# PickPlaceFeederSCH.net
KiCad netlist of a schematic drawn in Altium Designer
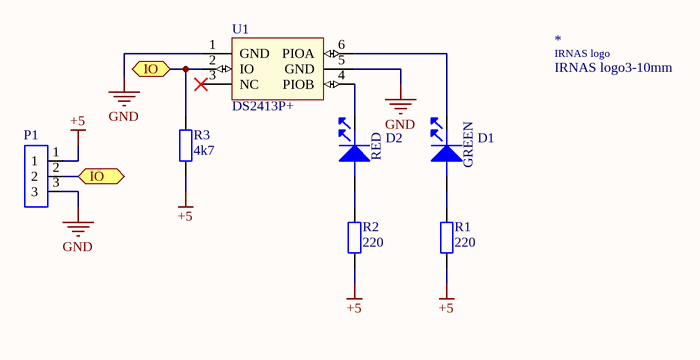
[diagram p0: PickPlaceFeederSCH.SchDoc]

(export (version "E")
  (design (tool "Eeschema 10.0.6"))
  (components
    (comp (ref "*")
      (value "IRNAS logo3-10mm")
      (footprint "LOGO_3-10mm")
      (libsource (lib "Graphical") (part "IRNAS logo3-10mm"))
    )
    (comp (ref "D1")
      (value "LED GREEN")
      (footprint "LED0603")
      (description "HSME-C191 -  LED, Green, SMD, 0603, 20 mA, 2.1 V, 572 nm")
      (fields
        (field (name "MANUFACTURER") "BROADCOM LIMITED")
        (field (name "MANUFACTURER PART NUMBER") "HSMS-C190")
      )
      (libsource (lib "Active") (part "LED - LED GREEN"))
    )
    (comp (ref "D2")
      (value "LED RED")
      (footprint "LED0603")
      (description "BROADCOM LIMITED - HSMS-C190 - LED, RED, 10MCD, 626NM")
      (fields
        (field (name "MANUFACTURER") "BROADCOM LIMITED")
        (field (name "MANUFACTURER PART NUMBER") "HSMS-C190")
      )
      (libsource (lib "Active") (part "LED - LED RED"))
    )
    (comp (ref "P1")
      (value "~")
      (footprint "Pogo_pin_3pos_90deg")
      (libsource (lib "Cerovsek_Library") (part "Pogo_pin_SMD [3 positions, 90deg, SMD]"))
    )
    (comp (ref "R1")
      (value "CRCW06030000Z0EAHP")
      (footprint "Res [0603/1608]")
      (description "Res Thick Film 0603 220 Ohm 5% 1/10W ±200ppm/°C Molded SMD Paper T/R")
      (fields
        (field (name "MANUFACTURER") "Vishay Dale")
        (field (name "RESISTANCE") "220")
        (field (name "TOLERANCE") "5%")
      )
      (libsource (lib "Cerovsek_Library") (part "Res_220_Ohm_[0603/1608]"))
    )
    (comp (ref "R2")
      (value "CRCW06030000Z0EAHP")
      (footprint "Res [0603/1608]")
      (description "Res Thick Film 0603 220 Ohm 5% 1/10W ±200ppm/°C Molded SMD Paper T/R")
      (fields
        (field (name "MANUFACTURER") "Vishay Dale")
        (field (name "RESISTANCE") "220")
        (field (name "TOLERANCE") "5%")
      )
      (libsource (lib "Cerovsek_Library") (part "Res_220_Ohm_[0603/1608]"))
    )
    (comp (ref "R3")
      (value "CRCW06034K70JNEA")
      (footprint "Res [0603/1608]")
      (description "Res Thick Film 0603 4.7 kOhm 5% 0.1W(1/10W) ±200ppm/°C Pad SMD T/R")
      (fields
        (field (name "MANUFACTURER") "Vishay")
        (field (name "RESISTANCE") "4k7")
        (field (name "TOLERANCE") "5%")
      )
      (libsource (lib "Cerovsek_Library") (part "Res_4k7_Ohm_[0603/1608]"))
    )
    (comp (ref "U1")
      (value "DS2413P+")
      (footprint "TSOC-6")
      (description "1-Wire, Dual-Channel, Addressable Switch Features Open-Drain, Programmable I/O Pins")
      (fields (field (name "MANUFACTURER") "Maxim"))
      (libsource (lib "Cerovsek_Library") (part "DS2413P+"))
    )
  )
  (nets
    (net (code "1") (name "+5") (class "Default")
      (node (ref "P1") (pin "1") (pinfunction "1_1") (pintype "passive"))
      (node (ref "R1") (pin "1") (pinfunction "1_1") (pintype "passive"))
      (node (ref "R2") (pin "1") (pinfunction "1_1") (pintype "passive"))
      (node (ref "R3") (pin "1") (pinfunction "1_1") (pintype "passive"))
    )
    (net (code "2") (name "/IO") (class "Default")
      (node (ref "P1") (pin "2") (pinfunction "2_2") (pintype "passive"))
      (node (ref "R3") (pin "2") (pinfunction "2_2") (pintype "passive"))
      (node (ref "U1") (pin "2") (pinfunction "IO_2") (pintype "bidirectional"))
    )
    (net (code "3") (name "GND") (class "Default")
      (node (ref "P1") (pin "3") (pinfunction "3_3") (pintype "passive"))
      (node (ref "U1") (pin "1") (pinfunction "GND_1") (pintype "power_in"))
      (node (ref "U1") (pin "5") (pinfunction "GND_5") (pintype "passive"))
    )
    (net (code "4") (name "Net-(D1-ANODE)") (class "Default")
      (node (ref "D1") (pin "2") (pinfunction "ANODE_2") (pintype "passive"))
      (node (ref "R1") (pin "2") (pinfunction "2_2") (pintype "passive"))
    )
    (net (code "5") (name "Net-(D1-cathode)") (class "Default")
      (node (ref "D1") (pin "1") (pinfunction "cathode_1") (pintype "passive"))
      (node (ref "U1") (pin "6") (pinfunction "PIOA_6") (pintype "bidirectional"))
    )
    (net (code "6") (name "Net-(D2-ANODE)") (class "Default")
      (node (ref "D2") (pin "2") (pinfunction "ANODE_2") (pintype "passive"))
      (node (ref "R2") (pin "2") (pinfunction "2_2") (pintype "passive"))
    )
    (net (code "7") (name "Net-(D2-cathode)") (class "Default")
      (node (ref "D2") (pin "1") (pinfunction "cathode_1") (pintype "passive"))
      (node (ref "U1") (pin "4") (pinfunction "PIOB_4") (pintype "bidirectional"))
    )
    (net (code "8") (name "unconnected-(U1-NC-Pad3)") (class "Default")
      (node (ref "U1") (pin "3") (pinfunction "NC_3") (pintype "passive+no_connect"))
    )
  )
)
